# RAIL_DISCHARGE.net
KiCad netlist of a schematic drawn in Altium Designer
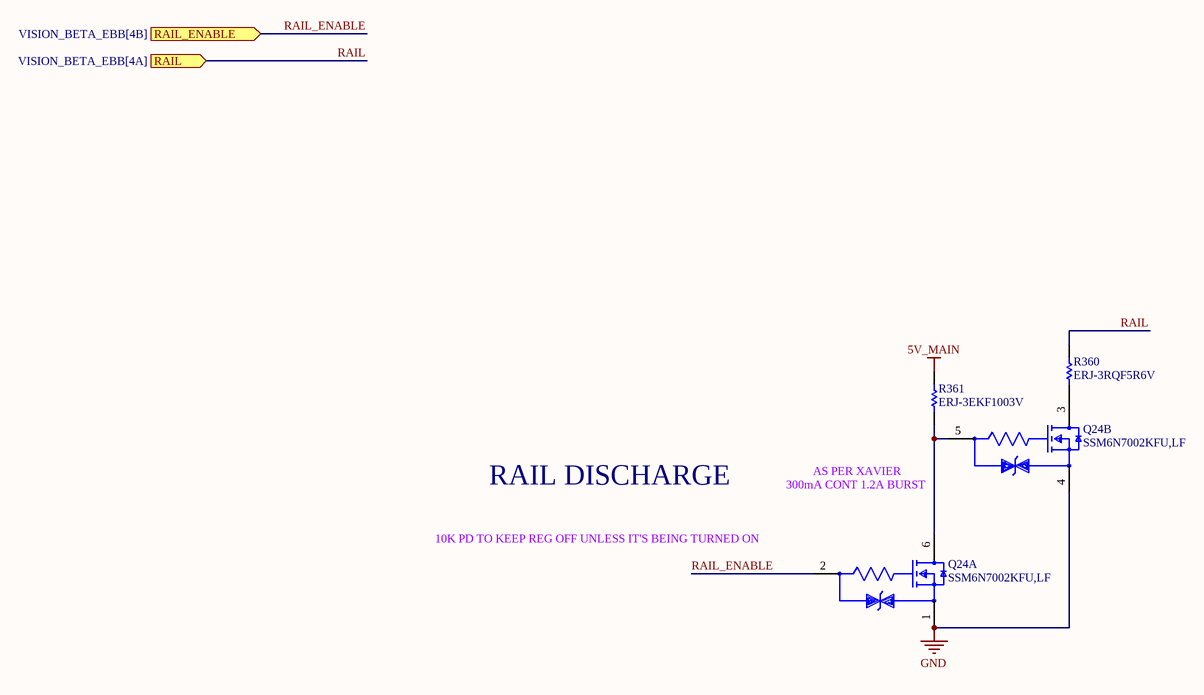
[diagram p0: RAIL_DISCHARGE.SchDoc]

(export (version "E")
  (design (tool "Eeschema 10.0.6"))
  (components
    (comp (ref "Q24")
      (value "SSM6N7002KFU,LF")
      (footprint "FP-SSOP6-P-0_65A-MFG")
      (description "MOSFET 2N-CH 60V 0.3A")
      (libsource (lib "Altium Content Vault") (part "088aa6ac103fdeebe0d1c52ece6b7b9"))
    )
    (comp (ref "R360")
      (value "ERJ-3RQF5R6V")
      (footprint "RESC1608X55X30LL15T15")
      (fields (field (name "MANUFACTURER") "Panasonic"))
      (libsource (lib "Altium Content Vault") (part "RES"))
    )
    (comp (ref "R361")
      (value "ERJ-3EKF1003V")
      (footprint "RESC1608X55X30ML15T15")
      (fields (field (name "MANUFACTURER") "Panasonic"))
      (libsource (lib "Altium Content Vault") (part "RES"))
    )
  )
  (nets
    (net (code "1") (name "/RAIL") (class "Default")
      (node (ref "R360") (pin "2") (pinfunction "2_2") (pintype "passive"))
    )
    (net (code "2") (name "/RAIL_ENABLE") (class "Default")
      (node (ref "Q24") (pin "2") (pinfunction "Gate1_2") (pintype "passive"))
    )
    (net (code "3") (name "5V_MAIN") (class "Default")
      (node (ref "R361") (pin "2") (pinfunction "2_2") (pintype "passive"))
    )
    (net (code "4") (name "GND") (class "Default")
      (node (ref "Q24") (pin "1") (pinfunction "Source1_1") (pintype "passive"))
      (node (ref "Q24") (pin "4") (pinfunction "Source2_4") (pintype "passive"))
    )
    (net (code "5") (name "Net-(Q24A-Drain1)") (class "Default")
      (node (ref "Q24") (pin "5") (pinfunction "Gate2_5") (pintype "passive"))
      (node (ref "Q24") (pin "6") (pinfunction "Drain1_6") (pintype "passive"))
      (node (ref "R361") (pin "1") (pinfunction "1_1") (pintype "passive"))
    )
    (net (code "6") (name "Net-(Q24B-Drain2)") (class "Default")
      (node (ref "Q24") (pin "3") (pinfunction "Drain2_3") (pintype "passive"))
      (node (ref "R360") (pin "1") (pinfunction "1_1") (pintype "passive"))
    )
  )
)
